# followLineSensor.net
KiCad netlist of a schematic drawn in EAGLE
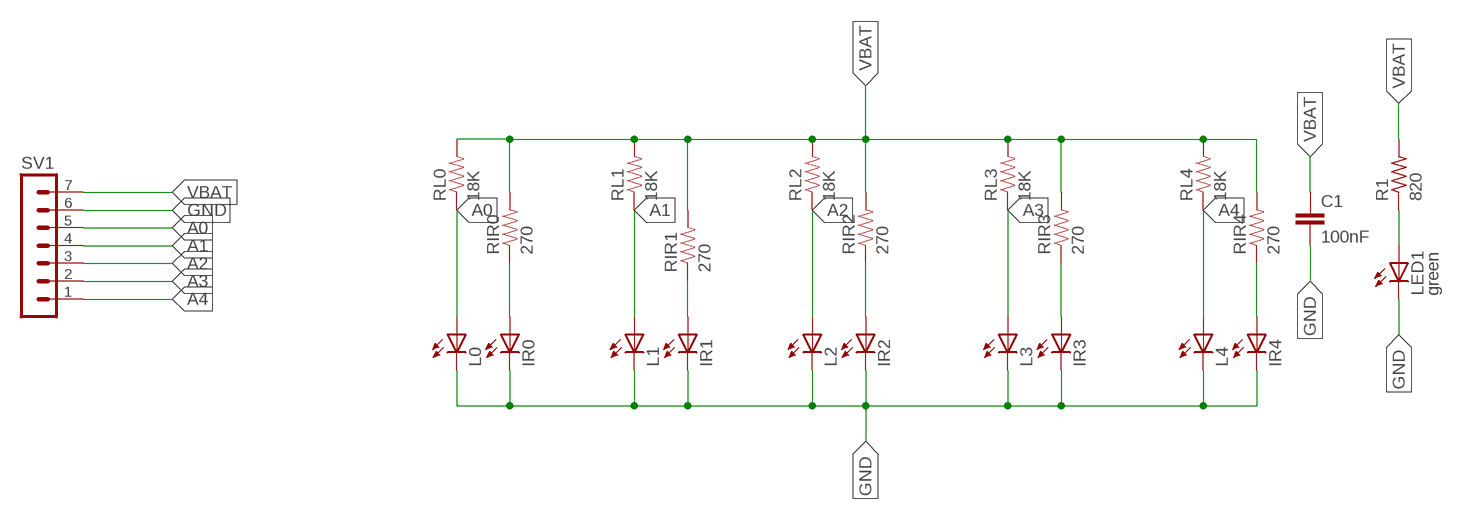
[diagram p0: schematic, sheet 1]

(export (version "E")
  (design (tool "Eeschema 10.0.6"))
  (components
    (comp (ref "C1")
      (value "100nF")
      (footprint "eagle-import:C0805")
      (libsource (lib "eagle-import") (part "C-EUC0805"))
    )
    (comp (ref "IR0")
      (value "LED5MM")
      (footprint "eagle-import:LED5MM")
      (libsource (lib "eagle-import") (part "LED5MM"))
    )
    (comp (ref "IR1")
      (value "LED5MM")
      (footprint "eagle-import:LED5MM")
      (libsource (lib "eagle-import") (part "LED5MM"))
    )
    (comp (ref "IR2")
      (value "LED5MM")
      (footprint "eagle-import:LED5MM")
      (libsource (lib "eagle-import") (part "LED5MM"))
    )
    (comp (ref "IR3")
      (value "LED5MM")
      (footprint "eagle-import:LED5MM")
      (libsource (lib "eagle-import") (part "LED5MM"))
    )
    (comp (ref "IR4")
      (value "LED5MM")
      (footprint "eagle-import:LED5MM")
      (libsource (lib "eagle-import") (part "LED5MM"))
    )
    (comp (ref "L0")
      (value "LED5MM")
      (footprint "eagle-import:LED5MM")
      (libsource (lib "eagle-import") (part "LED5MM"))
    )
    (comp (ref "L1")
      (value "LED5MM")
      (footprint "eagle-import:LED5MM")
      (libsource (lib "eagle-import") (part "LED5MM"))
    )
    (comp (ref "L2")
      (value "LED5MM")
      (footprint "eagle-import:LED5MM")
      (libsource (lib "eagle-import") (part "LED5MM"))
    )
    (comp (ref "L3")
      (value "LED5MM")
      (footprint "eagle-import:LED5MM")
      (libsource (lib "eagle-import") (part "LED5MM"))
    )
    (comp (ref "L4")
      (value "LED5MM")
      (footprint "eagle-import:LED5MM")
      (libsource (lib "eagle-import") (part "LED5MM"))
    )
    (comp (ref "LED1")
      (value "green")
      (footprint "eagle-import:SML0805")
      (libsource (lib "eagle-import") (part "LEDSML0805"))
    )
    (comp (ref "R1")
      (value "820")
      (footprint "eagle-import:R0805")
      (libsource (lib "eagle-import") (part "R-US_R0805"))
    )
    (comp (ref "RIR0")
      (value "270")
      (footprint "eagle-import:1206")
      (libsource (lib "eagle-import") (part "RESISTOR1206"))
    )
    (comp (ref "RIR1")
      (value "270")
      (footprint "eagle-import:1206")
      (libsource (lib "eagle-import") (part "RESISTOR1206"))
    )
    (comp (ref "RIR2")
      (value "270")
      (footprint "eagle-import:1206")
      (libsource (lib "eagle-import") (part "RESISTOR1206"))
    )
    (comp (ref "RIR3")
      (value "270")
      (footprint "eagle-import:1206")
      (libsource (lib "eagle-import") (part "RESISTOR1206"))
    )
    (comp (ref "RIR4")
      (value "270")
      (footprint "eagle-import:1206")
      (libsource (lib "eagle-import") (part "RESISTOR1206"))
    )
    (comp (ref "RL0")
      (value "18K")
      (footprint "eagle-import:1206")
      (libsource (lib "eagle-import") (part "RESISTOR1206"))
    )
    (comp (ref "RL1")
      (value "18K")
      (footprint "eagle-import:1206")
      (libsource (lib "eagle-import") (part "RESISTOR1206"))
    )
    (comp (ref "RL2")
      (value "18K")
      (footprint "eagle-import:1206")
      (libsource (lib "eagle-import") (part "RESISTOR1206"))
    )
    (comp (ref "RL3")
      (value "18K")
      (footprint "eagle-import:1206")
      (libsource (lib "eagle-import") (part "RESISTOR1206"))
    )
    (comp (ref "RL4")
      (value "18K")
      (footprint "eagle-import:1206")
      (libsource (lib "eagle-import") (part "RESISTOR1206"))
    )
    (comp (ref "SV1")
      (value "MA07-1")
      (footprint "eagle-import:MA07-1")
      (libsource (lib "eagle-import") (part "MA07-1"))
    )
  )
  (nets
    (net (code "1") (name "A0") (class "Default")
      (node (ref "L0") (pin "A") (pinfunction "A_A") (pintype "passive"))
      (node (ref "RL0") (pin "1") (pinfunction "1_1") (pintype "passive"))
      (node (ref "SV1") (pin "5") (pinfunction "5_5") (pintype "passive"))
    )
    (net (code "2") (name "A1") (class "Default")
      (node (ref "L1") (pin "A") (pinfunction "A_A") (pintype "passive"))
      (node (ref "RL1") (pin "1") (pinfunction "1_1") (pintype "passive"))
      (node (ref "SV1") (pin "4") (pinfunction "4_4") (pintype "passive"))
    )
    (net (code "3") (name "A2") (class "Default")
      (node (ref "L2") (pin "A") (pinfunction "A_A") (pintype "passive"))
      (node (ref "RL2") (pin "1") (pinfunction "1_1") (pintype "passive"))
      (node (ref "SV1") (pin "3") (pinfunction "3_3") (pintype "passive"))
    )
    (net (code "4") (name "A3") (class "Default")
      (node (ref "L3") (pin "A") (pinfunction "A_A") (pintype "passive"))
      (node (ref "RL3") (pin "1") (pinfunction "1_1") (pintype "passive"))
      (node (ref "SV1") (pin "2") (pinfunction "2_2") (pintype "passive"))
    )
    (net (code "5") (name "A4") (class "Default")
      (node (ref "L4") (pin "A") (pinfunction "A_A") (pintype "passive"))
      (node (ref "RL4") (pin "1") (pinfunction "1_1") (pintype "passive"))
      (node (ref "SV1") (pin "1") (pinfunction "1_1") (pintype "passive"))
    )
    (net (code "6") (name "GND") (class "Default")
      (node (ref "C1") (pin "2") (pinfunction "2_2") (pintype "passive"))
      (node (ref "IR0") (pin "K") (pinfunction "C_K") (pintype "passive"))
      (node (ref "IR1") (pin "K") (pinfunction "C_K") (pintype "passive"))
      (node (ref "IR2") (pin "K") (pinfunction "C_K") (pintype "passive"))
      (node (ref "IR3") (pin "K") (pinfunction "C_K") (pintype "passive"))
      (node (ref "IR4") (pin "K") (pinfunction "C_K") (pintype "passive"))
      (node (ref "L0") (pin "K") (pinfunction "C_K") (pintype "passive"))
      (node (ref "L1") (pin "K") (pinfunction "C_K") (pintype "passive"))
      (node (ref "L2") (pin "K") (pinfunction "C_K") (pintype "passive"))
      (node (ref "L3") (pin "K") (pinfunction "C_K") (pintype "passive"))
      (node (ref "L4") (pin "K") (pinfunction "C_K") (pintype "passive"))
      (node (ref "LED1") (pin "C") (pinfunction "C_C") (pintype "passive"))
      (node (ref "SV1") (pin "6") (pinfunction "6_6") (pintype "passive"))
    )
    (net (code "7") (name "Net-(IR0-PadA)") (class "Default")
      (node (ref "IR0") (pin "A") (pinfunction "A_A") (pintype "passive"))
      (node (ref "RIR0") (pin "1") (pinfunction "1_1") (pintype "passive"))
    )
    (net (code "8") (name "Net-(IR1-PadA)") (class "Default")
      (node (ref "IR1") (pin "A") (pinfunction "A_A") (pintype "passive"))
      (node (ref "RIR1") (pin "1") (pinfunction "1_1") (pintype "passive"))
    )
    (net (code "9") (name "Net-(IR2-PadA)") (class "Default")
      (node (ref "IR2") (pin "A") (pinfunction "A_A") (pintype "passive"))
      (node (ref "RIR2") (pin "1") (pinfunction "1_1") (pintype "passive"))
    )
    (net (code "10") (name "Net-(IR3-PadA)") (class "Default")
      (node (ref "IR3") (pin "A") (pinfunction "A_A") (pintype "passive"))
      (node (ref "RIR3") (pin "1") (pinfunction "1_1") (pintype "passive"))
    )
    (net (code "11") (name "Net-(IR4-PadA)") (class "Default")
      (node (ref "IR4") (pin "A") (pinfunction "A_A") (pintype "passive"))
      (node (ref "RIR4") (pin "1") (pinfunction "1_1") (pintype "passive"))
    )
    (net (code "12") (name "Net-(LED1-PadA)") (class "Default")
      (node (ref "LED1") (pin "A") (pinfunction "A_A") (pintype "passive"))
      (node (ref "R1") (pin "1") (pinfunction "1_1") (pintype "passive"))
    )
    (net (code "13") (name "VBAT") (class "Default")
      (node (ref "C1") (pin "1") (pinfunction "1_1") (pintype "passive"))
      (node (ref "R1") (pin "2") (pinfunction "2_2") (pintype "passive"))
      (node (ref "RIR0") (pin "2") (pinfunction "2_2") (pintype "passive"))
      (node (ref "RIR1") (pin "2") (pinfunction "2_2") (pintype "passive"))
      (node (ref "RIR2") (pin "2") (pinfunction "2_2") (pintype "passive"))
      (node (ref "RIR3") (pin "2") (pinfunction "2_2") (pintype "passive"))
      (node (ref "RIR4") (pin "2") (pinfunction "2_2") (pintype "passive"))
      (node (ref "RL0") (pin "2") (pinfunction "2_2") (pintype "passive"))
      (node (ref "RL1") (pin "2") (pinfunction "2_2") (pintype "passive"))
      (node (ref "RL2") (pin "2") (pinfunction "2_2") (pintype "passive"))
      (node (ref "RL3") (pin "2") (pinfunction "2_2") (pintype "passive"))
      (node (ref "RL4") (pin "2") (pinfunction "2_2") (pintype "passive"))
      (node (ref "SV1") (pin "7") (pinfunction "7_7") (pintype "passive"))
    )
  )
)
